# Analog_SCH4.net
KiCad netlist of a schematic drawn in Altium Designer
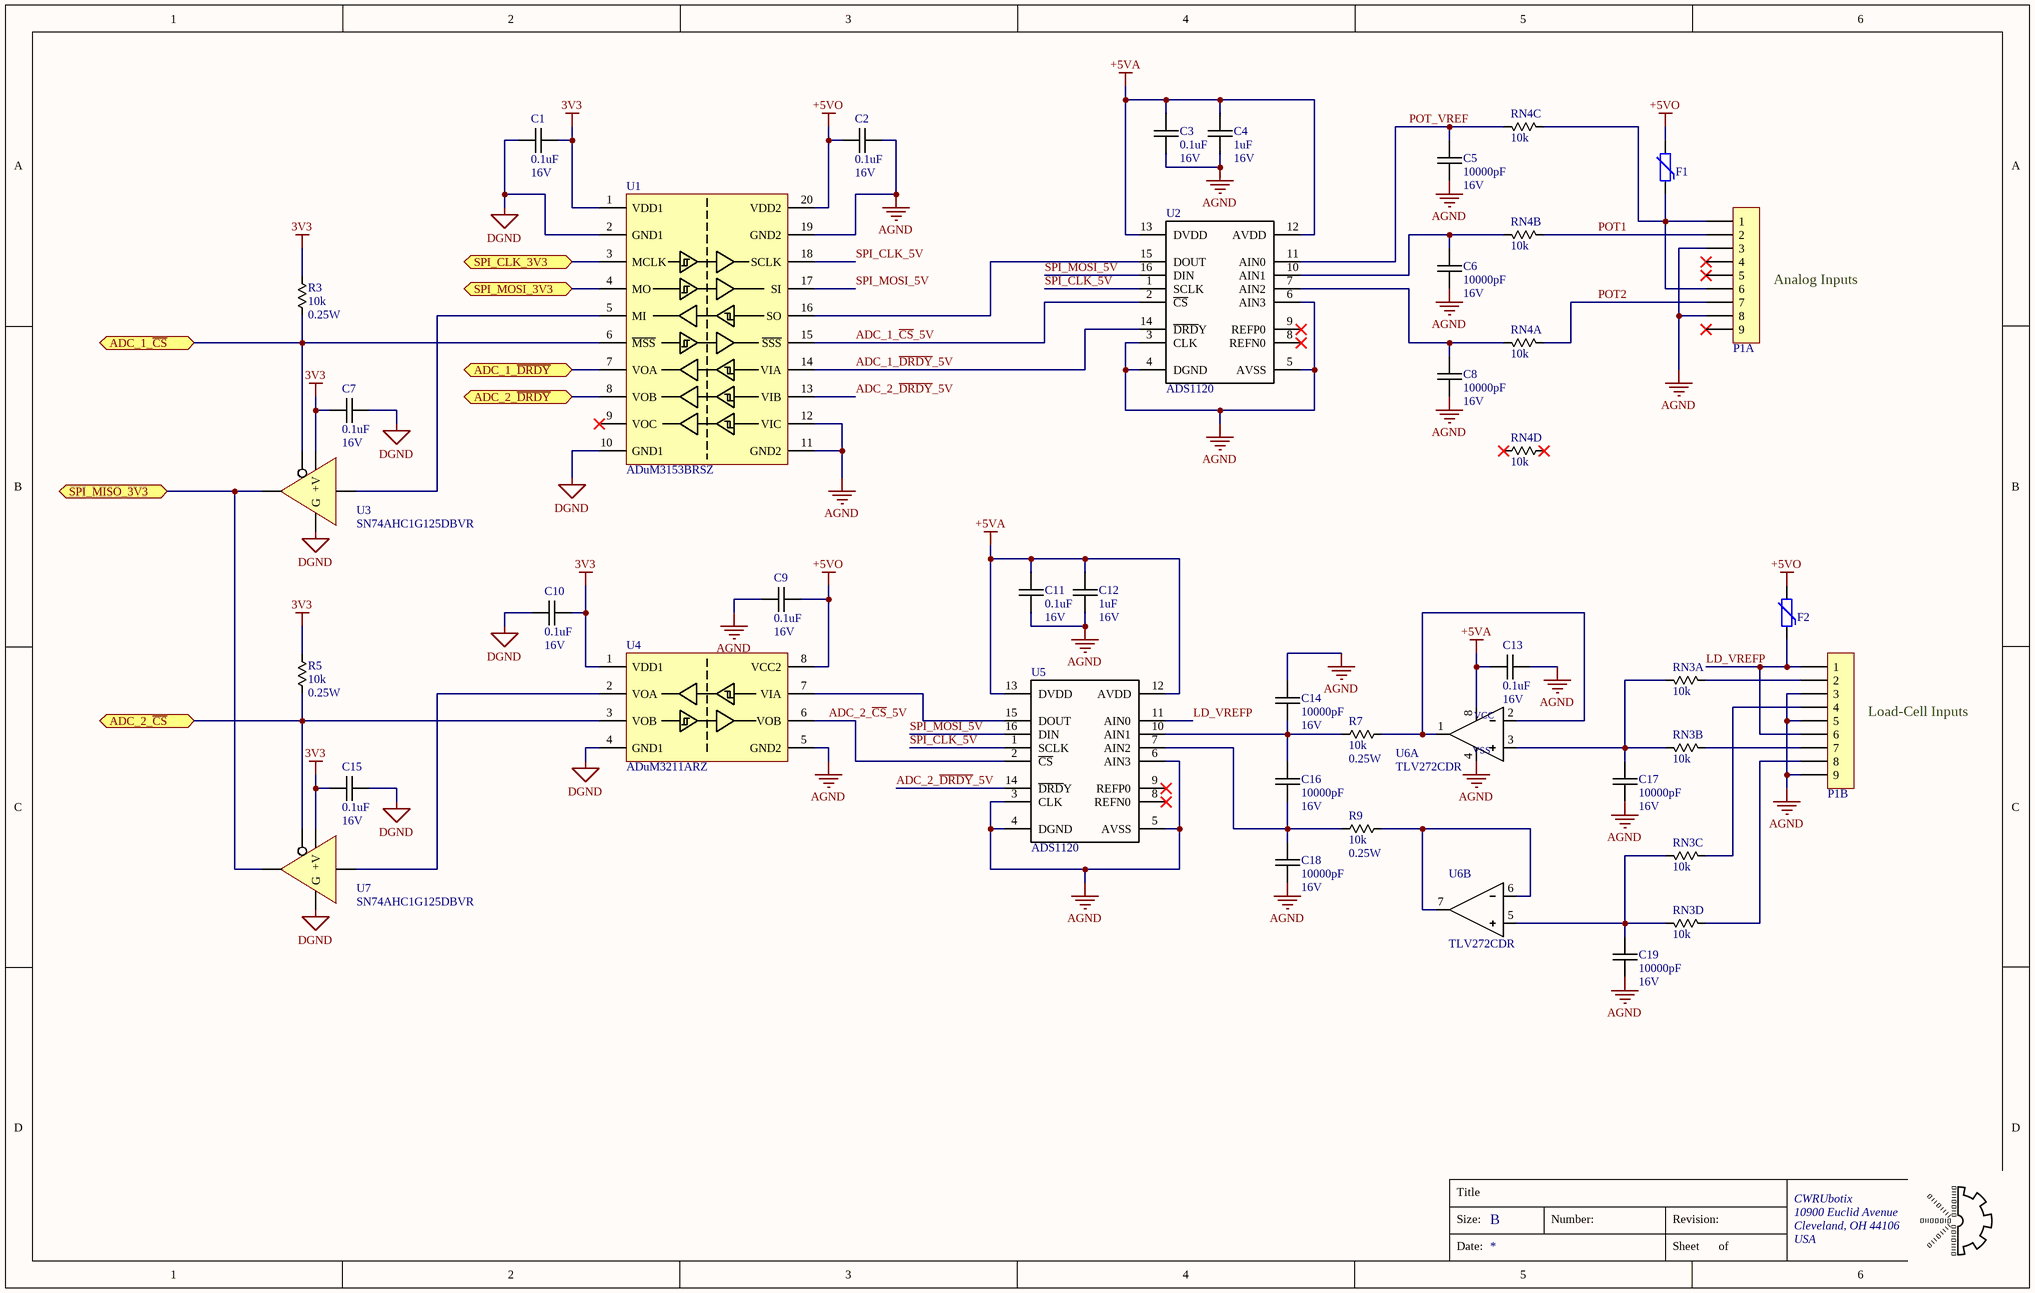
[diagram p0: Analog_SCH4.SchDoc]

(export (version "E")
  (design (tool "Eeschema 10.0.6"))
  (components
    (comp (ref "C1")
      (value "cap_single_np")
      (footprint "chip_0603")
      (description "CAP, 0.1uF, ±10%, 16V, X7R, 0603")
      (fields
        (field (name "TOLERANCE") "±10%")
        (field (name "CAPACITANCE") "0.1uF")
        (field (name "VOLTAGE RATING") "16V")
        (field (name "PART NUMBER") "CAP-00542")
      )
      (libsource (lib "Capacitors") (part "cap_single_np"))
    )
    (comp (ref "C2")
      (value "cap_single_np")
      (footprint "chip_0603")
      (description "CAP, 0.1uF, ±10%, 16V, X7R, 0603")
      (fields
        (field (name "TOLERANCE") "±10%")
        (field (name "CAPACITANCE") "0.1uF")
        (field (name "VOLTAGE RATING") "16V")
        (field (name "PART NUMBER") "CAP-00542")
      )
      (libsource (lib "Capacitors") (part "cap_single_np"))
    )
    (comp (ref "C3")
      (value "cap_single_np")
      (footprint "chip_0603")
      (description "CAP, 0.1uF, ±10%, 16V, X7R, 0603")
      (fields
        (field (name "TOLERANCE") "±10%")
        (field (name "CAPACITANCE") "0.1uF")
        (field (name "VOLTAGE RATING") "16V")
        (field (name "PART NUMBER") "CAP-00542")
      )
      (libsource (lib "Capacitors") (part "cap_single_np"))
    )
    (comp (ref "C4")
      (value "cap_single_np")
      (footprint "chip_0805")
      (description "CAP, 1uF, 10%, 16V, X7R, 0805")
      (fields
        (field (name "TOLERANCE") "10%")
        (field (name "CAPACITANCE") "1uF")
        (field (name "VOLTAGE RATING") "16V")
        (field (name "PART NUMBER") "CAP-00107")
      )
      (libsource (lib "Capacitors") (part "cap_single_np"))
    )
    (comp (ref "C5")
      (value "cap_single_np")
      (footprint "chip_0603")
      (description "CAP, 10000pF, ±10%, 16V, X7R, 0603")
      (fields
        (field (name "TOLERANCE") "±10%")
        (field (name "CAPACITANCE") "10000pF")
        (field (name "VOLTAGE RATING") "16V")
        (field (name "PART NUMBER") "CAP-00543")
      )
      (libsource (lib "Capacitors") (part "cap_single_np"))
    )
    (comp (ref "C6")
      (value "cap_single_np")
      (footprint "chip_0603")
      (description "CAP, 10000pF, ±10%, 16V, X7R, 0603")
      (fields
        (field (name "TOLERANCE") "±10%")
        (field (name "CAPACITANCE") "10000pF")
        (field (name "VOLTAGE RATING") "16V")
        (field (name "PART NUMBER") "CAP-00543")
      )
      (libsource (lib "Capacitors") (part "cap_single_np"))
    )
    (comp (ref "C7")
      (value "cap_single_np")
      (footprint "chip_0603")
      (description "CAP, 0.1uF, ±10%, 16V, X7R, 0603")
      (fields
        (field (name "TOLERANCE") "±10%")
        (field (name "CAPACITANCE") "0.1uF")
        (field (name "VOLTAGE RATING") "16V")
        (field (name "PART NUMBER") "CAP-00542")
      )
      (libsource (lib "Capacitors") (part "cap_single_np"))
    )
    (comp (ref "C8")
      (value "cap_single_np")
      (footprint "chip_0603")
      (description "CAP, 10000pF, ±10%, 16V, X7R, 0603")
      (fields
        (field (name "TOLERANCE") "±10%")
        (field (name "CAPACITANCE") "10000pF")
        (field (name "VOLTAGE RATING") "16V")
        (field (name "PART NUMBER") "CAP-00543")
      )
      (libsource (lib "Capacitors") (part "cap_single_np"))
    )
    (comp (ref "C9")
      (value "cap_single_np")
      (footprint "chip_0603")
      (description "CAP, 0.1uF, ±10%, 16V, X7R, 0603")
      (fields
        (field (name "TOLERANCE") "±10%")
        (field (name "CAPACITANCE") "0.1uF")
        (field (name "VOLTAGE RATING") "16V")
        (field (name "PART NUMBER") "CAP-00542")
      )
      (libsource (lib "Capacitors") (part "cap_single_np"))
    )
    (comp (ref "C10")
      (value "cap_single_np")
      (footprint "chip_0603")
      (description "CAP, 0.1uF, ±10%, 16V, X7R, 0603")
      (fields
        (field (name "TOLERANCE") "±10%")
        (field (name "CAPACITANCE") "0.1uF")
        (field (name "VOLTAGE RATING") "16V")
        (field (name "PART NUMBER") "CAP-00542")
      )
      (libsource (lib "Capacitors") (part "cap_single_np"))
    )
    (comp (ref "C11")
      (value "cap_single_np")
      (footprint "chip_0603")
      (description "CAP, 0.1uF, ±10%, 16V, X7R, 0603")
      (fields
        (field (name "TOLERANCE") "±10%")
        (field (name "CAPACITANCE") "0.1uF")
        (field (name "VOLTAGE RATING") "16V")
        (field (name "PART NUMBER") "CAP-00542")
      )
      (libsource (lib "Capacitors") (part "cap_single_np"))
    )
    (comp (ref "C12")
      (value "cap_single_np")
      (footprint "chip_0805")
      (description "CAP, 1uF, 10%, 16V, X7R, 0805")
      (fields
        (field (name "TOLERANCE") "10%")
        (field (name "CAPACITANCE") "1uF")
        (field (name "VOLTAGE RATING") "16V")
        (field (name "PART NUMBER") "CAP-00107")
      )
      (libsource (lib "Capacitors") (part "cap_single_np"))
    )
    (comp (ref "C13")
      (value "cap_single_np")
      (footprint "chip_0603")
      (description "CAP, 0.1uF, ±10%, 16V, X7R, 0603")
      (fields
        (field (name "TOLERANCE") "±10%")
        (field (name "CAPACITANCE") "0.1uF")
        (field (name "VOLTAGE RATING") "16V")
        (field (name "PART NUMBER") "CAP-00542")
      )
      (libsource (lib "Capacitors") (part "cap_single_np"))
    )
    (comp (ref "C14")
      (value "cap_single_np")
      (footprint "chip_0603")
      (description "CAP, 10000pF, ±10%, 16V, X7R, 0603")
      (fields
        (field (name "TOLERANCE") "±10%")
        (field (name "CAPACITANCE") "10000pF")
        (field (name "VOLTAGE RATING") "16V")
        (field (name "PART NUMBER") "CAP-00543")
      )
      (libsource (lib "Capacitors") (part "cap_single_np"))
    )
    (comp (ref "C15")
      (value "cap_single_np")
      (footprint "chip_0603")
      (description "CAP, 0.1uF, ±10%, 16V, X7R, 0603")
      (fields
        (field (name "TOLERANCE") "±10%")
        (field (name "CAPACITANCE") "0.1uF")
        (field (name "VOLTAGE RATING") "16V")
        (field (name "PART NUMBER") "CAP-00542")
      )
      (libsource (lib "Capacitors") (part "cap_single_np"))
    )
    (comp (ref "C16")
      (value "cap_single_np")
      (footprint "chip_0603")
      (description "CAP, 10000pF, ±10%, 16V, X7R, 0603")
      (fields
        (field (name "TOLERANCE") "±10%")
        (field (name "CAPACITANCE") "10000pF")
        (field (name "VOLTAGE RATING") "16V")
        (field (name "PART NUMBER") "CAP-00543")
      )
      (libsource (lib "Capacitors") (part "cap_single_np"))
    )
    (comp (ref "C17")
      (value "cap_single_np")
      (footprint "chip_0603")
      (description "CAP, 10000pF, ±10%, 16V, X7R, 0603")
      (fields
        (field (name "TOLERANCE") "±10%")
        (field (name "CAPACITANCE") "10000pF")
        (field (name "VOLTAGE RATING") "16V")
        (field (name "PART NUMBER") "CAP-00543")
      )
      (libsource (lib "Capacitors") (part "cap_single_np"))
    )
    (comp (ref "C18")
      (value "cap_single_np")
      (footprint "chip_0603")
      (description "CAP, 10000pF, ±10%, 16V, X7R, 0603")
      (fields
        (field (name "TOLERANCE") "±10%")
        (field (name "CAPACITANCE") "10000pF")
        (field (name "VOLTAGE RATING") "16V")
        (field (name "PART NUMBER") "CAP-00543")
      )
      (libsource (lib "Capacitors") (part "cap_single_np"))
    )
    (comp (ref "C19")
      (value "cap_single_np")
      (footprint "chip_0603")
      (description "CAP, 10000pF, ±10%, 16V, X7R, 0603")
      (fields
        (field (name "TOLERANCE") "±10%")
        (field (name "CAPACITANCE") "10000pF")
        (field (name "VOLTAGE RATING") "16V")
        (field (name "PART NUMBER") "CAP-00543")
      )
      (libsource (lib "Capacitors") (part "cap_single_np"))
    )
    (comp (ref "F1")
      (value "PTC_0")
      (footprint "chip_1206")
      (description "PTC Resettable fuse, 6V, 500mA, 1206")
      (fields (field (name "PART NUMBER") "MISC-00008") (field (name "MANUFACTURER") "Eaton"))
      (libsource (lib "Misc") (part "PTC_0"))
    )
    (comp (ref "F2")
      (value "PTC_0")
      (footprint "chip_1206")
      (description "PTC Resettable fuse, 6V, 500mA, 1206")
      (fields (field (name "PART NUMBER") "MISC-00008") (field (name "MANUFACTURER") "Eaton"))
      (libsource (lib "Misc") (part "PTC_0"))
    )
    (comp (ref "P1")
      (value "conn-9x1_x2")
      (footprint "D_SUB_9x2_0")
      (description "D-Sub, Dual 9-pin")
      (fields (field (name "PART NUMBER") "CONN-00025") (field (name "MANUFACTURER") "NorComp"))
      (libsource (lib "Connectors") (part "conn-9x1_x2"))
    )
    (comp (ref "R3")
      (value "res_single")
      (footprint "chip_0603")
      (description "RES SMD 10K OHM 1% 1/4W 0603")
      (fields
        (field (name "TOLERANCE") "1%")
        (field (name "RESISTANCE") "10k")
        (field (name "POWER RATING") "0.25W")
        (field (name "PART NUMBER") "RES-00306")
      )
      (libsource (lib "Resistors") (part "res_single"))
    )
    (comp (ref "R5")
      (value "res_single")
      (footprint "chip_0603")
      (description "RES SMD 10K OHM 1% 1/4W 0603")
      (fields
        (field (name "TOLERANCE") "1%")
        (field (name "RESISTANCE") "10k")
        (field (name "POWER RATING") "0.25W")
        (field (name "PART NUMBER") "RES-00306")
      )
      (libsource (lib "Resistors") (part "res_single"))
    )
    (comp (ref "R7")
      (value "res_single")
      (footprint "chip_0603")
      (description "RES SMD 10K OHM 1% 1/4W 0603")
      (fields
        (field (name "TOLERANCE") "1%")
        (field (name "RESISTANCE") "10k")
        (field (name "POWER RATING") "0.25W")
        (field (name "PART NUMBER") "RES-00306")
      )
      (libsource (lib "Resistors") (part "res_single"))
    )
    (comp (ref "R9")
      (value "res_single")
      (footprint "chip_0603")
      (description "RES SMD 10K OHM 1% 1/4W 0603")
      (fields
        (field (name "TOLERANCE") "1%")
        (field (name "RESISTANCE") "10k")
        (field (name "POWER RATING") "0.25W")
        (field (name "PART NUMBER") "RES-00306")
      )
      (libsource (lib "Resistors") (part "res_single"))
    )
    (comp (ref "RN3")
      (value "res_array_4")
      (footprint "chip_1206_arr")
      (description "RES ARRAY 4 RES 10k OHM 5% 1/16W 1206")
      (fields
        (field (name "RESISTANCE") "10k")
        (field (name "PART NUMBER") "RES-00697")
        (field (name "TOLERANCE") "0.05")
      )
      (libsource (lib "Resistors") (part "res_array_4"))
    )
    (comp (ref "RN4")
      (value "res_array_4")
      (footprint "chip_1206_arr")
      (description "RES ARRAY 4 RES 10k OHM 5% 1/16W 1206")
      (fields
        (field (name "RESISTANCE") "10k")
        (field (name "PART NUMBER") "RES-00697")
        (field (name "TOLERANCE") "0.05")
      )
      (libsource (lib "Resistors") (part "res_array_4"))
    )
    (comp (ref "U1")
      (value "ADuM3153")
      (footprint "tssop-20_0")
      (description "Digital Isolator, SPI-bus optomized, ADuM3153")
      (fields
        (field (name "MANUFACTURER PN") "ADuM3153BRSZ")
        (field (name "PART NUMBER") "IFACE-00014")
        (field (name "MANUFACTURER") "Analog Devices")
      )
      (libsource (lib "Interfaces") (part "ADuM3153"))
    )
    (comp (ref "U2")
      (value "ADS1120")
      (footprint "tssop-16_0")
      (description "ADC, 16-bit, 4-channel, SPI, 2k SPS, TSSOP-16")
      (fields (field (name "PART NUMBER") "ANLG-00016") (field (name "MANUFACTURER") "TI"))
      (libsource (lib "Analog") (part "ADS1120"))
    )
    (comp (ref "U3")
      (value "SN74AHCT1G125")
      (footprint "sot-23-5")
      (description "Tri-State Buffer, Single, 2-5.5V, SOT-23-5, SN74AHC1G125")
      (fields
        (field (name "MANUFACTURER PN") "SN74AHC1G125DBVR")
        (field (name "PART NUMBER") "LOGIC-00027")
        (field (name "MANUFACTURER") "TI")
      )
      (libsource (lib "Logic") (part "SN74AHCT1G125"))
    )
    (comp (ref "U4")
      (value "ADuM3211")
      (footprint "SO-8")
      (description "Digital Isolator, Dual-Channel, ADuM3211")
      (fields
        (field (name "MANUFACTURER PN") "ADuM3211ARZ")
        (field (name "PART NUMBER") "IFACE-00015")
        (field (name "MANUFACTURER") "Analog Devices")
      )
      (libsource (lib "Interfaces") (part "ADuM3211"))
    )
    (comp (ref "U5")
      (value "ADS1120")
      (footprint "tssop-16_0")
      (description "ADC, 16-bit, 4-channel, SPI, 2k SPS, TSSOP-16")
      (fields (field (name "PART NUMBER") "ANLG-00016") (field (name "MANUFACTURER") "TI"))
      (libsource (lib "Analog") (part "ADS1120"))
    )
    (comp (ref "U6")
      (value "TLV272DGK")
      (footprint "so-8")
      (description "Op Amp, Dual, Rail-Rail, 3MHZ, SOIC-8")
      (fields
        (field (name "MANUFACTURER PN") "TLV272CDR")
        (field (name "PART NUMBER") "ANLG-00030")
        (field (name "MANUFACTURER") "TI")
      )
      (libsource (lib "Analog") (part "TLV272DGK"))
    )
    (comp (ref "U7")
      (value "SN74AHCT1G125")
      (footprint "sot-23-5")
      (description "Tri-State Buffer, Single, 2-5.5V, SOT-23-5, SN74AHC1G125")
      (fields
        (field (name "MANUFACTURER PN") "SN74AHC1G125DBVR")
        (field (name "PART NUMBER") "LOGIC-00027")
        (field (name "MANUFACTURER") "TI")
      )
      (libsource (lib "Logic") (part "SN74AHCT1G125"))
    )
  )
  (nets
    (net (code "1") (name "+5VA") (class "Default")
      (node (ref "C11") (pin "1") (pinfunction "1_1") (pintype "passive"))
      (node (ref "C12") (pin "2") (pinfunction "2_2") (pintype "passive"))
      (node (ref "C13") (pin "2") (pinfunction "2_2") (pintype "passive"))
      (node (ref "C3") (pin "1") (pinfunction "1_1") (pintype "passive"))
      (node (ref "C4") (pin "2") (pinfunction "2_2") (pintype "passive"))
      (node (ref "U2") (pin "12") (pinfunction "AVDD_12") (pintype "passive"))
      (node (ref "U2") (pin "13") (pinfunction "DVDD_13") (pintype "passive"))
      (node (ref "U5") (pin "12") (pinfunction "AVDD_12") (pintype "passive"))
      (node (ref "U5") (pin "13") (pinfunction "DVDD_13") (pintype "passive"))
      (node (ref "U6") (pin "8") (pinfunction "8_8") (pintype "passive"))
    )
    (net (code "2") (name "+5VO") (class "Default")
      (node (ref "C2") (pin "1") (pinfunction "1_1") (pintype "passive"))
      (node (ref "C9") (pin "2") (pinfunction "2_2") (pintype "passive"))
      (node (ref "F1") (pin "2") (pinfunction "2_2") (pintype "passive"))
      (node (ref "F2") (pin "2") (pinfunction "2_2") (pintype "passive"))
      (node (ref "U1") (pin "20") (pinfunction "VDD2_20") (pintype "passive"))
      (node (ref "U4") (pin "8") (pinfunction "VCC2_8") (pintype "passive"))
    )
    (net (code "3") (name "/ADC_1_~{CS}") (class "Default")
      (node (ref "R3") (pin "1") (pinfunction "1_1") (pintype "passive"))
      (node (ref "U1") (pin "6") (pinfunction "~{MSS}_6") (pintype "passive"))
      (node (ref "U3") (pin "1") (pinfunction "~{OE}_1") (pintype "passive"))
    )
    (net (code "4") (name "/ADC_1_~{CS}_5V") (class "Default")
      (node (ref "U1") (pin "15") (pinfunction "~{SSS}_15") (pintype "passive"))
      (node (ref "U2") (pin "2") (pinfunction "~{CS}_2") (pintype "passive"))
    )
    (net (code "5") (name "/ADC_1_~{DRDY}") (class "Default")
      (node (ref "U1") (pin "7") (pinfunction "VOA_7") (pintype "passive"))
    )
    (net (code "6") (name "/ADC_1_~{DRDY}_5V") (class "Default")
      (node (ref "U1") (pin "14") (pinfunction "VIA_14") (pintype "passive"))
      (node (ref "U2") (pin "14") (pinfunction "~{DRD}Y_14") (pintype "passive"))
    )
    (net (code "7") (name "/ADC_2_~{CS}") (class "Default")
      (node (ref "R5") (pin "1") (pinfunction "1_1") (pintype "passive"))
      (node (ref "U4") (pin "3") (pinfunction "VOB_3") (pintype "passive"))
      (node (ref "U7") (pin "1") (pinfunction "~{OE}_1") (pintype "passive"))
    )
    (net (code "8") (name "/ADC_2_~{CS}_5V") (class "Default")
      (node (ref "U4") (pin "6") (pinfunction "VOB_6") (pintype "passive"))
      (node (ref "U5") (pin "2") (pinfunction "~{CS}_2") (pintype "passive"))
    )
    (net (code "9") (name "/ADC_2_~{DRDY}") (class "Default")
      (node (ref "U1") (pin "8") (pinfunction "VOB_8") (pintype "passive"))
    )
    (net (code "10") (name "/ADC_2_~{DRDY}_5V") (class "Default")
      (node (ref "U1") (pin "13") (pinfunction "VIB_13") (pintype "passive"))
      (node (ref "U5") (pin "14") (pinfunction "~{DRD}Y_14") (pintype "passive"))
    )
    (net (code "11") (name "/LD_VREFP") (class "Default")
      (node (ref "F2") (pin "1") (pinfunction "1_1") (pintype "passive"))
      (node (ref "P1") (pin "10") (pinfunction "1_10") (pintype "passive"))
      (node (ref "P1") (pin "15") (pinfunction "6_15") (pintype "passive"))
      (node (ref "U5") (pin "11") (pinfunction "AIN0_11") (pintype "passive"))
    )
    (net (code "12") (name "/POT1") (class "Default")
      (node (ref "P1") (pin "2") (pinfunction "2_2") (pintype "passive"))
      (node (ref "RN4") (pin "2") (pinfunction "2_2") (pintype "passive"))
    )
    (net (code "13") (name "/POT2") (class "Default")
      (node (ref "P1") (pin "7") (pinfunction "7_7") (pintype "passive"))
      (node (ref "RN4") (pin "1") (pinfunction "1_1") (pintype "passive"))
    )
    (net (code "14") (name "/POT_VREF") (class "Default")
      (node (ref "C5") (pin "1") (pinfunction "1_1") (pintype "passive"))
      (node (ref "RN4") (pin "6") (pinfunction "6_6") (pintype "passive"))
      (node (ref "U2") (pin "11") (pinfunction "AIN0_11") (pintype "passive"))
    )
    (net (code "15") (name "/SPI_CLK_3V3") (class "Default")
      (node (ref "U1") (pin "3") (pinfunction "MCLK_3") (pintype "passive"))
    )
    (net (code "16") (name "/SPI_CLK_5V") (class "Default")
      (node (ref "U1") (pin "18") (pinfunction "SCLK_18") (pintype "passive"))
      (node (ref "U2") (pin "1") (pinfunction "SCLK_1") (pintype "passive"))
      (node (ref "U5") (pin "1") (pinfunction "SCLK_1") (pintype "passive"))
    )
    (net (code "17") (name "/SPI_MISO_3V3") (class "Default")
      (node (ref "U3") (pin "4") (pinfunction "Y_4") (pintype "passive"))
      (node (ref "U7") (pin "4") (pinfunction "Y_4") (pintype "passive"))
    )
    (net (code "18") (name "/SPI_MOSI_3V3") (class "Default")
      (node (ref "U1") (pin "4") (pinfunction "MO_4") (pintype "passive"))
    )
    (net (code "19") (name "/SPI_MOSI_5V") (class "Default")
      (node (ref "U1") (pin "17") (pinfunction "SI_17") (pintype "passive"))
      (node (ref "U2") (pin "16") (pinfunction "DIN_16") (pintype "passive"))
      (node (ref "U5") (pin "16") (pinfunction "DIN_16") (pintype "passive"))
    )
    (net (code "20") (name "3V3") (class "Default")
      (node (ref "C1") (pin "2") (pinfunction "2_2") (pintype "passive"))
      (node (ref "C10") (pin "2") (pinfunction "2_2") (pintype "passive"))
      (node (ref "C15") (pin "2") (pinfunction "2_2") (pintype "passive"))
      (node (ref "C7") (pin "2") (pinfunction "2_2") (pintype "passive"))
      (node (ref "R3") (pin "2") (pinfunction "2_2") (pintype "passive"))
      (node (ref "R5") (pin "2") (pinfunction "2_2") (pintype "passive"))
      (node (ref "U1") (pin "1") (pinfunction "VDD1_1") (pintype "passive"))
      (node (ref "U3") (pin "5") (pinfunction "+V_5") (pintype "passive"))
      (node (ref "U4") (pin "1") (pinfunction "VDD1_1") (pintype "passive"))
      (node (ref "U7") (pin "5") (pinfunction "+V_5") (pintype "passive"))
    )
    (net (code "21") (name "AGND") (class "Default")
      (node (ref "C11") (pin "2") (pinfunction "2_2") (pintype "passive"))
      (node (ref "C12") (pin "1") (pinfunction "1_1") (pintype "passive"))
      (node (ref "C13") (pin "1") (pinfunction "1_1") (pintype "passive"))
      (node (ref "C14") (pin "1") (pinfunction "1_1") (pintype "passive"))
      (node (ref "C17") (pin "2") (pinfunction "2_2") (pintype "passive"))
      (node (ref "C18") (pin "2") (pinfunction "2_2") (pintype "passive"))
      (node (ref "C19") (pin "2") (pinfunction "2_2") (pintype "passive"))
      (node (ref "C2") (pin "2") (pinfunction "2_2") (pintype "passive"))
      (node (ref "C3") (pin "2") (pinfunction "2_2") (pintype "passive"))
      (node (ref "C4") (pin "1") (pinfunction "1_1") (pintype "passive"))
      (node (ref "C5") (pin "2") (pinfunction "2_2") (pintype "passive"))
      (node (ref "C6") (pin "2") (pinfunction "2_2") (pintype "passive"))
      (node (ref "C8") (pin "2") (pinfunction "2_2") (pintype "passive"))
      (node (ref "C9") (pin "1") (pinfunction "1_1") (pintype "passive"))
      (node (ref "P1") (pin "12") (pinfunction "3_12") (pintype "passive"))
      (node (ref "P1") (pin "14") (pinfunction "5_14") (pintype "passive"))
      (node (ref "P1") (pin "18") (pinfunction "9_18") (pintype "passive"))
      (node (ref "P1") (pin "3") (pinfunction "3_3") (pintype "passive"))
      (node (ref "P1") (pin "8") (pinfunction "8_8") (pintype "passive"))
      (node (ref "U1") (pin "11") (pinfunction "GND2_11") (pintype "passive"))
      (node (ref "U1") (pin "12") (pinfunction "VIC_12") (pintype "passive"))
      (node (ref "U1") (pin "19") (pinfunction "GND2_19") (pintype "passive"))
      (node (ref "U2") (pin "3") (pinfunction "CLK_3") (pintype "passive"))
      (node (ref "U2") (pin "4") (pinfunction "DGND_4") (pintype "passive"))
      (node (ref "U2") (pin "5") (pinfunction "AVSS_5") (pintype "passive"))
      (node (ref "U2") (pin "6") (pinfunction "AIN3_6") (pintype "passive"))
      (node (ref "U4") (pin "5") (pinfunction "GND2_5") (pintype "passive"))
      (node (ref "U5") (pin "3") (pinfunction "CLK_3") (pintype "passive"))
      (node (ref "U5") (pin "4") (pinfunction "DGND_4") (pintype "passive"))
      (node (ref "U5") (pin "5") (pinfunction "AVSS_5") (pintype "passive"))
      (node (ref "U5") (pin "6") (pinfunction "AIN3_6") (pintype "passive"))
      (node (ref "U6") (pin "4") (pinfunction "4_4") (pintype "passive"))
    )
    (net (code "22") (name "DGND") (class "Default")
      (node (ref "C1") (pin "1") (pinfunction "1_1") (pintype "passive"))
      (node (ref "C10") (pin "1") (pinfunction "1_1") (pintype "passive"))
      (node (ref "C15") (pin "1") (pinfunction "1_1") (pintype "passive"))
      (node (ref "C7") (pin "1") (pinfunction "1_1") (pintype "passive"))
      (node (ref "U1") (pin "10") (pinfunction "GND1_10") (pintype "passive"))
      (node (ref "U1") (pin "2") (pinfunction "GND1_2") (pintype "passive"))
      (node (ref "U3") (pin "3") (pinfunction "G_3") (pintype "passive"))
      (node (ref "U4") (pin "4") (pinfunction "GND1_4") (pintype "passive"))
      (node (ref "U7") (pin "3") (pinfunction "G_3") (pintype "passive"))
    )
    (net (code "23") (name "Net-(C17-Pad1)") (class "Default")
      (node (ref "C17") (pin "1") (pinfunction "1_1") (pintype "passive"))
      (node (ref "RN3") (pin "7") (pinfunction "7_7") (pintype "passive"))
      (node (ref "RN3") (pin "8") (pinfunction "8_8") (pintype "passive"))
      (node (ref "U6") (pin "3") (pinfunction "3_3") (pintype "passive"))
    )
    (net (code "24") (name "Net-(C19-Pad1)") (class "Default")
      (node (ref "C19") (pin "1") (pinfunction "1_1") (pintype "passive"))
      (node (ref "RN3") (pin "5") (pinfunction "5_5") (pintype "passive"))
      (node (ref "RN3") (pin "6") (pinfunction "6_6") (pintype "passive"))
      (node (ref "U6") (pin "5") (pinfunction "5_5") (pintype "passive"))
    )
    (net (code "25") (name "Net-(F1-Pad1)") (class "Default")
      (node (ref "F1") (pin "1") (pinfunction "1_1") (pintype "passive"))
      (node (ref "P1") (pin "1") (pinfunction "1_1") (pintype "passive"))
      (node (ref "P1") (pin "6") (pinfunction "6_6") (pintype "passive"))
      (node (ref "RN4") (pin "3") (pinfunction "3_3") (pintype "passive"))
    )
    (net (code "26") (name "Net-(P1B-2)") (class "Default")
      (node (ref "P1") (pin "11") (pinfunction "2_11") (pintype "passive"))
      (node (ref "RN3") (pin "1") (pinfunction "1_1") (pintype "passive"))
    )
    (net (code "27") (name "Net-(P1B-4)") (class "Default")
      (node (ref "P1") (pin "13") (pinfunction "4_13") (pintype "passive"))
      (node (ref "RN3") (pin "3") (pinfunction "3_3") (pintype "passive"))
    )
    (net (code "28") (name "Net-(P1B-7)") (class "Default")
      (node (ref "P1") (pin "16") (pinfunction "7_16") (pintype "passive"))
      (node (ref "RN3") (pin "2") (pinfunction "2_2") (pintype "passive"))
    )
    (net (code "29") (name "Net-(P1B-8)") (class "Default")
      (node (ref "P1") (pin "17") (pinfunction "8_17") (pintype "passive"))
      (node (ref "RN3") (pin "4") (pinfunction "4_4") (pintype "passive"))
    )
    (net (code "30") (name "Net-(R7-Pad2)") (class "Default")
      (node (ref "R7") (pin "2") (pinfunction "2_2") (pintype "passive"))
      (node (ref "U6") (pin "1") (pinfunction "1_1") (pintype "passive"))
      (node (ref "U6") (pin "2") (pinfunction "2_2") (pintype "passive"))
    )
    (net (code "31") (name "Net-(R9-Pad2)") (class "Default")
      (node (ref "R9") (pin "2") (pinfunction "2_2") (pintype "passive"))
      (node (ref "U6") (pin "6") (pinfunction "6_6") (pintype "passive"))
      (node (ref "U6") (pin "7") (pinfunction "7_7") (pintype "passive"))
    )
    (net (code "32") (name "Net-(U1-MI)") (class "Default")
      (node (ref "U1") (pin "5") (pinfunction "MI_5") (pintype "passive"))
      (node (ref "U3") (pin "2") (pinfunction "A_2") (pintype "passive"))
    )
    (net (code "33") (name "Net-(U1-SO)") (class "Default")
      (node (ref "U1") (pin "16") (pinfunction "SO_16") (pintype "passive"))
      (node (ref "U2") (pin "15") (pinfunction "DOUT_15") (pintype "passive"))
    )
    (net (code "34") (name "Net-(U2-AIN1)") (class "Default")
      (node (ref "C6") (pin "1") (pinfunction "1_1") (pintype "passive"))
      (node (ref "RN4") (pin "7") (pinfunction "7_7") (pintype "passive"))
      (node (ref "U2") (pin "10") (pinfunction "AIN1_10") (pintype "passive"))
    )
    (net (code "35") (name "Net-(U2-AIN2)") (class "Default")
      (node (ref "C8") (pin "1") (pinfunction "1_1") (pintype "passive"))
      (node (ref "RN4") (pin "8") (pinfunction "8_8") (pintype "passive"))
      (node (ref "U2") (pin "7") (pinfunction "AIN2_7") (pintype "passive"))
    )
    (net (code "36") (name "Net-(U4-VIA)") (class "Default")
      (node (ref "U4") (pin "7") (pinfunction "VIA_7") (pintype "passive"))
      (node (ref "U5") (pin "15") (pinfunction "DOUT_15") (pintype "passive"))
    )
    (net (code "37") (name "Net-(U4-VOA)") (class "Default")
      (node (ref "U4") (pin "2") (pinfunction "VOA_2") (pintype "passive"))
      (node (ref "U7") (pin "2") (pinfunction "A_2") (pintype "passive"))
    )
    (net (code "38") (name "Net-(U5-AIN1)") (class "Default")
      (node (ref "C14") (pin "2") (pinfunction "2_2") (pintype "passive"))
      (node (ref "C16") (pin "1") (pinfunction "1_1") (pintype "passive"))
      (node (ref "R7") (pin "1") (pinfunction "1_1") (pintype "passive"))
      (node (ref "U5") (pin "10") (pinfunction "AIN1_10") (pintype "passive"))
    )
    (net (code "39") (name "Net-(U5-AIN2)") (class "Default")
      (node (ref "C16") (pin "2") (pinfunction "2_2") (pintype "passive"))
      (node (ref "C18") (pin "1") (pinfunction "1_1") (pintype "passive"))
      (node (ref "R9") (pin "1") (pinfunction "1_1") (pintype "passive"))
      (node (ref "U5") (pin "7") (pinfunction "AIN2_7") (pintype "passive"))
    )
    (net (code "40") (name "unconnected-(P1-Pad4)") (class "Default")
      (node (ref "P1") (pin "4") (pinfunction "4_4") (pintype "passive+no_connect"))
    )
    (net (code "41") (name "unconnected-(P1-Pad5)") (class "Default")
      (node (ref "P1") (pin "5") (pinfunction "5_5") (pintype "passive+no_connect"))
    )
    (net (code "42") (name "unconnected-(P1-Pad9)") (class "Default")
      (node (ref "P1") (pin "9") (pinfunction "9_9") (pintype "passive+no_connect"))
    )
    (net (code "43") (name "unconnected-(RN4-Pad4)") (class "Default")
      (node (ref "RN4") (pin "4") (pinfunction "4_4") (pintype "passive+no_connect"))
    )
    (net (code "44") (name "unconnected-(RN4-Pad5)") (class "Default")
      (node (ref "RN4") (pin "5") (pinfunction "5_5") (pintype "passive+no_connect"))
    )
    (net (code "45") (name "unconnected-(U1-VOC-Pad9)") (class "Default")
      (node (ref "U1") (pin "9") (pinfunction "VOC_9") (pintype "passive+no_connect"))
    )
    (net (code "46") (name "unconnected-(U2-REFN0-Pad8)") (class "Default")
      (node (ref "U2") (pin "8") (pinfunction "REFN0_8") (pintype "passive+no_connect"))
    )
    (net (code "47") (name "unconnected-(U2-REFP0-Pad9)") (class "Default")
      (node (ref "U2") (pin "9") (pinfunction "REFP0_9") (pintype "passive+no_connect"))
    )
    (net (code "48") (name "unconnected-(U5-REFN0-Pad8)") (class "Default")
      (node (ref "U5") (pin "8") (pinfunction "REFN0_8") (pintype "passive+no_connect"))
    )
    (net (code "49") (name "unconnected-(U5-REFP0-Pad9)") (class "Default")
      (node (ref "U5") (pin "9") (pinfunction "REFP0_9") (pintype "passive+no_connect"))
    )
  )
)
